# joint_board_can.net
KiCad netlist of a schematic drawn in Altium Designer
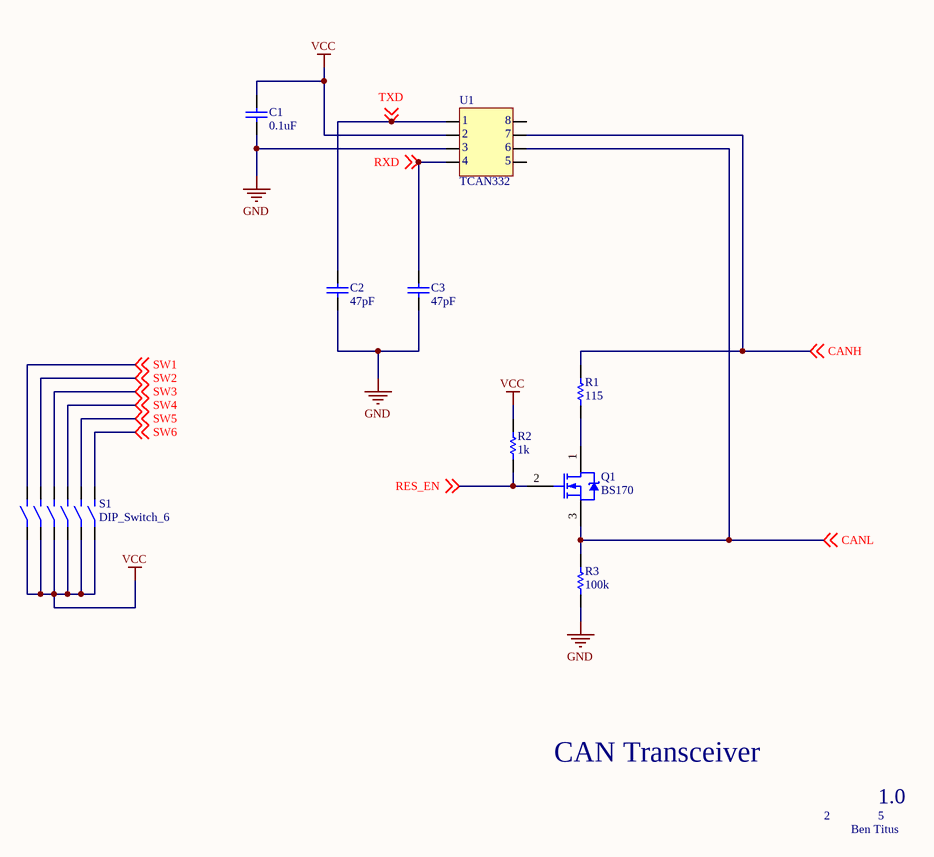
[diagram p0: joint_board_can.SchDoc]

(export (version "E")
  (design (tool "Eeschema 10.0.6"))
  (components
    (comp (ref "C1")
      (value "0.1uF")
      (footprint "CAPC0805(2012)145_L")
      (description "0805 (2012 Metric) Chip Capacitor")
      (libsource (lib "Altium Content Vault") (part "CAP_5"))
    )
    (comp (ref "C2")
      (value "47pF")
      (footprint "CAPC0805(2012)145_L")
      (description "0805 (2012 Metric) Chip Capacitor")
      (libsource (lib "Altium Content Vault") (part "CAP_5"))
    )
    (comp (ref "C3")
      (value "47pF")
      (footprint "CAPC0805(2012)145_L")
      (description "0805 (2012 Metric) Chip Capacitor")
      (libsource (lib "Altium Content Vault") (part "CAP_5"))
    )
    (comp (ref "Q1")
      (value "BS170")
      (footprint "SOT23-3")
      (description "Small Signal MOSFET, 500 mA, 60 V, N-Channel, 3-Pin TO-92, Bulk Box")
      (fields (field (name "MANUFACTURER") "On Semiconductor"))
      (libsource (lib "ON Semi MOSFETs") (part "BS170"))
    )
    (comp (ref "R1")
      (value "115")
      (footprint "RESC0805(2012)_L")
      (description "0805 (2012 Metric) Chip Resistor")
      (libsource (lib "Altium Content Vault") (part "RES_3"))
    )
    (comp (ref "R2")
      (value "1k")
      (footprint "RESC0805(2012)_L")
      (description "0805 (2012 Metric) Chip Resistor")
      (libsource (lib "Altium Content Vault") (part "RES_3"))
    )
    (comp (ref "R3")
      (value "100k")
      (footprint "RESC0805(2012)_L")
      (description "0805 (2012 Metric) Chip Resistor")
      (libsource (lib "Altium Content Vault") (part "RES_3"))
    )
    (comp (ref "S1")
      (value "DIP_Switch_6")
      (footprint "SOP12")
      (description "6 pin DIP switch")
      (libsource (lib "Custom_Lib") (part "DIP_Switch_6"))
    )
    (comp (ref "U1")
      (value "TCAN332")
      (footprint "SOP8")
      (description "3.3V CAN Transceiver")
      (libsource (lib "TCAN332") (part "TCAN332"))
    )
  )
  (nets
    (net (code "1") (name "CANH") (class "Default")
      (node (ref "R1") (pin "2") (pinfunction "2_2") (pintype "passive"))
      (node (ref "U1") (pin "7") (pintype "passive"))
    )
    (net (code "2") (name "CANL") (class "Default")
      (node (ref "Q1") (pin "3") (pinfunction "S_3") (pintype "passive"))
      (node (ref "R3") (pin "2") (pinfunction "2_2") (pintype "passive"))
      (node (ref "U1") (pin "6") (pintype "passive"))
    )
    (net (code "3") (name "GND") (class "Default")
      (node (ref "C1") (pin "1") (pinfunction "1_1") (pintype "passive"))
      (node (ref "C2") (pin "1") (pinfunction "1_1") (pintype "passive"))
      (node (ref "C3") (pin "1") (pinfunction "1_1") (pintype "passive"))
      (node (ref "R3") (pin "1") (pinfunction "1_1") (pintype "passive"))
      (node (ref "U1") (pin "3") (pintype "passive"))
    )
    (net (code "4") (name "Net-(Q1-D)") (class "Default")
      (node (ref "Q1") (pin "1") (pinfunction "D_1") (pintype "passive"))
      (node (ref "R1") (pin "1") (pinfunction "1_1") (pintype "passive"))
    )
    (net (code "5") (name "RES_EN") (class "Default")
      (node (ref "Q1") (pin "2") (pinfunction "G_2") (pintype "passive"))
      (node (ref "R2") (pin "1") (pinfunction "1_1") (pintype "passive"))
    )
    (net (code "6") (name "RXD") (class "Default")
      (node (ref "C3") (pin "2") (pinfunction "2_2") (pintype "passive"))
      (node (ref "U1") (pin "4") (pintype "passive"))
    )
    (net (code "7") (name "SW1") (class "Default") (node (ref "S1") (pin "12") (pintype "passive")))
    (net (code "8") (name "SW2") (class "Default") (node (ref "S1") (pin "11") (pintype "passive")))
    (net (code "9") (name "SW3") (class "Default") (node (ref "S1") (pin "10") (pintype "passive")))
    (net (code "10") (name "SW4") (class "Default") (node (ref "S1") (pin "9") (pintype "passive")))
    (net (code "11") (name "SW5") (class "Default") (node (ref "S1") (pin "8") (pintype "passive")))
    (net (code "12") (name "SW6") (class "Default") (node (ref "S1") (pin "7") (pintype "passive")))
    (net (code "13") (name "TXD") (class "Default")
      (node (ref "C2") (pin "2") (pinfunction "2_2") (pintype "passive"))
      (node (ref "U1") (pin "1") (pintype "passive"))
    )
    (net (code "14") (name "VCC") (class "Default")
      (node (ref "C1") (pin "2") (pinfunction "2_2") (pintype "passive"))
      (node (ref "R2") (pin "2") (pinfunction "2_2") (pintype "passive"))
      (node (ref "S1") (pin "1") (pintype "passive"))
      (node (ref "S1") (pin "2") (pintype "passive"))
      (node (ref "S1") (pin "3") (pintype "passive"))
      (node (ref "S1") (pin "4") (pintype "passive"))
      (node (ref "S1") (pin "5") (pintype "passive"))
      (node (ref "S1") (pin "6") (pintype "passive"))
      (node (ref "U1") (pin "2") (pintype "passive"))
    )
    (net (code "15") (name "unconnected-(U1-Pad5)") (class "Default")
      (node (ref "U1") (pin "5") (pintype "passive"))
    )
    (net (code "16") (name "unconnected-(U1-Pad8)") (class "Default")
      (node (ref "U1") (pin "8") (pintype "passive"))
    )
  )
)
